# 8_pin_plank.net
KiCad netlist of a schematic drawn in EAGLE
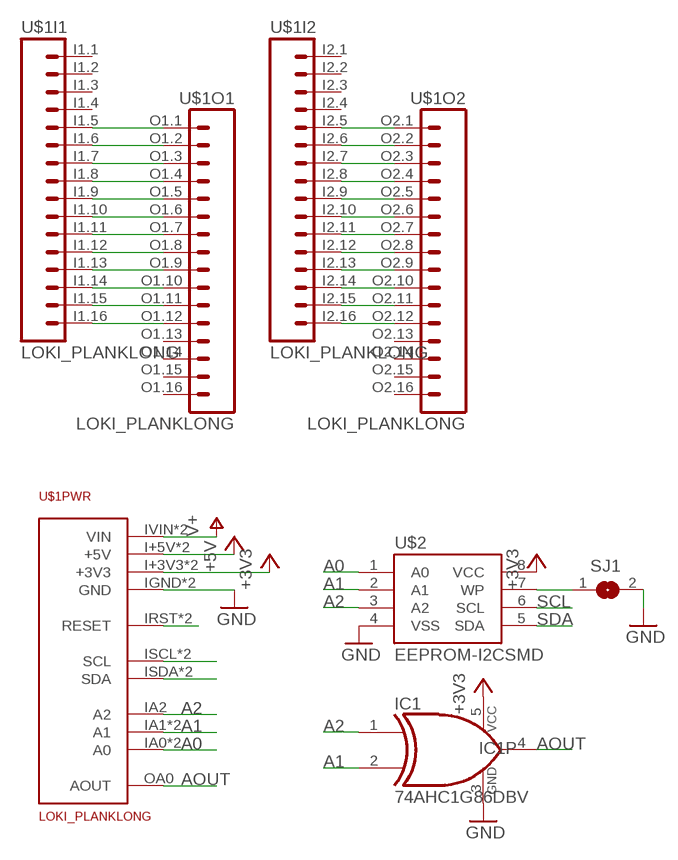
[diagram p0: schematic, sheet 1]

(export (version "E")
  (design (tool "Eeschema 10.0.6"))
  (components
    (comp (ref "IC1")
      (value "74AHC1G86DBV")
      (footprint "eagle-import:SOT23-5")
      (libsource (lib "eagle-import") (part "741G86DBVAHC"))
    )
    (comp (ref "SJ1") (value "SJ") (footprint "eagle-import:SJ") (libsource (lib "eagle-import") (part "SJ")))
    (comp (ref "U$1")
      (value "LOKI_PLANKLONG")
      (footprint "eagle-import:PLANK_LONG")
      (libsource (lib "eagle-import") (part "LOKI_PLANKLONG"))
    )
    (comp (ref "U$2")
      (value "EEPROM-I2CSMD")
      (footprint "eagle-import:SO08")
      (libsource (lib "eagle-import") (part "EEPROM-I2CSMD"))
    )
  )
  (nets
    (net (code "1") (name "+3V3") (class "Default")
      (node (ref "IC1") (pin "5") (pinfunction "VCC_5") (pintype "power_in"))
      (node (ref "U$1") (pin "I+3V3") (pinfunction "+3V3_I+3V3") (pintype "power_in"))
      (node (ref "U$1") (pin "O+3V3") (pinfunction "+3V3_O+3V3") (pintype "power_in"))
      (node (ref "U$2") (pin "8") (pinfunction "VCC_8") (pintype "power_in"))
    )
    (net (code "2") (name "+5V") (class "Default")
      (node (ref "U$1") (pin "I+5V") (pinfunction "+5V_I+5V") (pintype "power_in"))
      (node (ref "U$1") (pin "O+5V") (pinfunction "+5V_O+5V") (pintype "power_in"))
    )
    (net (code "3") (name "/A0") (class "Default")
      (node (ref "U$1") (pin "IA0") (pinfunction "A0_IA0") (pintype "output"))
      (node (ref "U$1") (pin "OA1") (pinfunction "A0_OA1") (pintype "output"))
      (node (ref "U$2") (pin "1") (pinfunction "A0_1") (pintype "bidirectional"))
    )
    (net (code "4") (name "/A1") (class "Default")
      (node (ref "IC1") (pin "2") (pinfunction "I1_2") (pintype "input"))
      (node (ref "U$1") (pin "IA1") (pinfunction "A1_IA1") (pintype "output"))
      (node (ref "U$1") (pin "OA2") (pinfunction "A1_OA2") (pintype "output"))
      (node (ref "U$2") (pin "2") (pinfunction "A1_2") (pintype "bidirectional"))
    )
    (net (code "5") (name "/A2") (class "Default")
      (node (ref "IC1") (pin "1") (pinfunction "I0_1") (pintype "input"))
      (node (ref "U$1") (pin "IA2") (pinfunction "A2_IA2") (pintype "output"))
      (node (ref "U$2") (pin "3") (pinfunction "A2_3") (pintype "bidirectional"))
    )
    (net (code "6") (name "/AOUT") (class "Default")
      (node (ref "IC1") (pin "4") (pinfunction "O_4") (pintype "output"))
      (node (ref "U$1") (pin "OA0") (pinfunction "AOUT_OA0") (pintype "input"))
    )
    (net (code "7") (name "/SCL") (class "Default")
      (node (ref "U$1") (pin "ISCL") (pinfunction "SCL_ISCL") (pintype "bidirectional"))
      (node (ref "U$1") (pin "OSCL") (pinfunction "SCL_OSCL") (pintype "bidirectional"))
      (node (ref "U$2") (pin "6") (pinfunction "SCL_6") (pintype "bidirectional"))
    )
    (net (code "8") (name "/SDA") (class "Default")
      (node (ref "U$1") (pin "ISDA") (pinfunction "SDA_ISDA") (pintype "bidirectional"))
      (node (ref "U$1") (pin "OSDA") (pinfunction "SDA_OSDA") (pintype "bidirectional"))
      (node (ref "U$2") (pin "5") (pinfunction "SDA_5") (pintype "bidirectional"))
    )
    (net (code "9") (name "GND") (class "Default")
      (node (ref "IC1") (pin "3") (pinfunction "GND_3") (pintype "power_in"))
      (node (ref "SJ1") (pin "2") (pinfunction "2_2") (pintype "passive"))
      (node (ref "U$1") (pin "IGND") (pinfunction "GND_IGND") (pintype "power_in"))
      (node (ref "U$1") (pin "OGND") (pinfunction "GND_OGND") (pintype "power_in"))
      (node (ref "U$2") (pin "4") (pinfunction "VSS_4") (pintype "power_in"))
    )
    (net (code "10") (name "Net-(U$1A-5)") (class "Default")
      (node (ref "U$1") (pin "I1.5") (pinfunction "5_I1.5") (pintype "passive"))
      (node (ref "U$1") (pin "O1.1") (pinfunction "1_O1.1") (pintype "passive"))
    )
    (net (code "11") (name "Net-(U$1A-6)") (class "Default")
      (node (ref "U$1") (pin "I1.6") (pinfunction "6_I1.6") (pintype "passive"))
      (node (ref "U$1") (pin "O1.2") (pinfunction "2_O1.2") (pintype "passive"))
    )
    (net (code "12") (name "Net-(U$1A-7)") (class "Default")
      (node (ref "U$1") (pin "I1.7") (pinfunction "7_I1.7") (pintype "passive"))
      (node (ref "U$1") (pin "O1.3") (pinfunction "3_O1.3") (pintype "passive"))
    )
    (net (code "13") (name "Net-(U$1A-8)") (class "Default")
      (node (ref "U$1") (pin "I1.8") (pinfunction "8_I1.8") (pintype "passive"))
      (node (ref "U$1") (pin "O1.4") (pinfunction "4_O1.4") (pintype "passive"))
    )
    (net (code "14") (name "Net-(U$1A-9)") (class "Default")
      (node (ref "U$1") (pin "I1.9") (pinfunction "9_I1.9") (pintype "passive"))
      (node (ref "U$1") (pin "O1.5") (pinfunction "5_O1.5") (pintype "passive"))
    )
    (net (code "15") (name "Net-(U$1A-10)") (class "Default")
      (node (ref "U$1") (pin "I1.10") (pinfunction "10_I1.10") (pintype "passive"))
      (node (ref "U$1") (pin "O1.6") (pinfunction "6_O1.6") (pintype "passive"))
    )
    (net (code "16") (name "Net-(U$1A-11)") (class "Default")
      (node (ref "U$1") (pin "I1.11") (pinfunction "11_I1.11") (pintype "passive"))
      (node (ref "U$1") (pin "O1.7") (pinfunction "7_O1.7") (pintype "passive"))
    )
    (net (code "17") (name "Net-(U$1A-12)") (class "Default")
      (node (ref "U$1") (pin "I1.12") (pinfunction "12_I1.12") (pintype "passive"))
      (node (ref "U$1") (pin "O1.8") (pinfunction "8_O1.8") (pintype "passive"))
    )
    (net (code "18") (name "Net-(U$1A-13)") (class "Default")
      (node (ref "U$1") (pin "I1.13") (pinfunction "13_I1.13") (pintype "passive"))
      (node (ref "U$1") (pin "O1.9") (pinfunction "9_O1.9") (pintype "passive"))
    )
    (net (code "19") (name "Net-(U$1A-14)") (class "Default")
      (node (ref "U$1") (pin "I1.14") (pinfunction "14_I1.14") (pintype "passive"))
      (node (ref "U$1") (pin "O1.10") (pinfunction "10_O1.10") (pintype "passive"))
    )
    (net (code "20") (name "Net-(U$1A-15)") (class "Default")
      (node (ref "U$1") (pin "I1.15") (pinfunction "15_I1.15") (pintype "passive"))
      (node (ref "U$1") (pin "O1.11") (pinfunction "11_O1.11") (pintype "passive"))
    )
    (net (code "21") (name "Net-(U$1A-16)") (class "Default")
      (node (ref "U$1") (pin "I1.16") (pinfunction "16_I1.16") (pintype "passive"))
      (node (ref "U$1") (pin "O1.12") (pinfunction "12_O1.12") (pintype "passive"))
    )
    (net (code "22") (name "Net-(U$1B-5)") (class "Default")
      (node (ref "U$1") (pin "I2.5") (pinfunction "5_I2.5") (pintype "passive"))
      (node (ref "U$1") (pin "O2.1") (pinfunction "1_O2.1") (pintype "passive"))
    )
    (net (code "23") (name "Net-(U$1B-6)") (class "Default")
      (node (ref "U$1") (pin "I2.6") (pinfunction "6_I2.6") (pintype "passive"))
      (node (ref "U$1") (pin "O2.2") (pinfunction "2_O2.2") (pintype "passive"))
    )
    (net (code "24") (name "Net-(U$1B-7)") (class "Default")
      (node (ref "U$1") (pin "I2.7") (pinfunction "7_I2.7") (pintype "passive"))
      (node (ref "U$1") (pin "O2.3") (pinfunction "3_O2.3") (pintype "passive"))
    )
    (net (code "25") (name "Net-(U$1B-8)") (class "Default")
      (node (ref "U$1") (pin "I2.8") (pinfunction "8_I2.8") (pintype "passive"))
      (node (ref "U$1") (pin "O2.4") (pinfunction "4_O2.4") (pintype "passive"))
    )
    (net (code "26") (name "Net-(U$1B-9)") (class "Default")
      (node (ref "U$1") (pin "I2.9") (pinfunction "9_I2.9") (pintype "passive"))
      (node (ref "U$1") (pin "O2.5") (pinfunction "5_O2.5") (pintype "passive"))
    )
    (net (code "27") (name "Net-(U$1B-10)") (class "Default")
      (node (ref "U$1") (pin "I2.10") (pinfunction "10_I2.10") (pintype "passive"))
      (node (ref "U$1") (pin "O2.6") (pinfunction "6_O2.6") (pintype "passive"))
    )
    (net (code "28") (name "Net-(U$1B-11)") (class "Default")
      (node (ref "U$1") (pin "I2.11") (pinfunction "11_I2.11") (pintype "passive"))
      (node (ref "U$1") (pin "O2.7") (pinfunction "7_O2.7") (pintype "passive"))
    )
    (net (code "29") (name "Net-(U$1B-12)") (class "Default")
      (node (ref "U$1") (pin "I2.12") (pinfunction "12_I2.12") (pintype "passive"))
      (node (ref "U$1") (pin "O2.8") (pinfunction "8_O2.8") (pintype "passive"))
    )
    (net (code "30") (name "Net-(U$1B-13)") (class "Default")
      (node (ref "U$1") (pin "I2.13") (pinfunction "13_I2.13") (pintype "passive"))
      (node (ref "U$1") (pin "O2.9") (pinfunction "9_O2.9") (pintype "passive"))
    )
    (net (code "31") (name "Net-(U$1B-14)") (class "Default")
      (node (ref "U$1") (pin "I2.14") (pinfunction "14_I2.14") (pintype "passive"))
      (node (ref "U$1") (pin "O2.10") (pinfunction "10_O2.10") (pintype "passive"))
    )
    (net (code "32") (name "Net-(U$1B-15)") (class "Default")
      (node (ref "U$1") (pin "I2.15") (pinfunction "15_I2.15") (pintype "passive"))
      (node (ref "U$1") (pin "O2.11") (pinfunction "11_O2.11") (pintype "passive"))
    )
    (net (code "33") (name "Net-(U$1B-16)") (class "Default")
      (node (ref "U$1") (pin "I2.16") (pinfunction "16_I2.16") (pintype "passive"))
      (node (ref "U$1") (pin "O2.12") (pinfunction "12_O2.12") (pintype "passive"))
    )
    (net (code "34") (name "Net-(U$1E-RESET-PadIRST)") (class "Default")
      (node (ref "U$1") (pin "IRST") (pinfunction "RESET_IRST") (pintype "input"))
      (node (ref "U$1") (pin "ORST") (pinfunction "RESET_ORST") (pintype "input"))
    )
    (net (code "35") (name "Net-(U$2-WP)") (class "Default")
      (node (ref "SJ1") (pin "1") (pinfunction "1_1") (pintype "passive"))
      (node (ref "U$2") (pin "7") (pinfunction "WP_7") (pintype "bidirectional"))
    )
    (net (code "36") (name "V+") (class "Default")
      (node (ref "U$1") (pin "IVIN") (pinfunction "VIN_IVIN") (pintype "power_in"))
      (node (ref "U$1") (pin "OVIN") (pinfunction "VIN_OVIN") (pintype "power_in"))
    )
    (net (code "37") (name "unconnected-(U$1A-1-PadI1.1)") (class "Default")
      (node (ref "U$1") (pin "I1.1") (pinfunction "1_I1.1") (pintype "passive"))
    )
    (net (code "38") (name "unconnected-(U$1A-2-PadI1.2)") (class "Default")
      (node (ref "U$1") (pin "I1.2") (pinfunction "2_I1.2") (pintype "passive"))
    )
    (net (code "39") (name "unconnected-(U$1A-3-PadI1.3)") (class "Default")
      (node (ref "U$1") (pin "I1.3") (pinfunction "3_I1.3") (pintype "passive"))
    )
    (net (code "40") (name "unconnected-(U$1A-4-PadI1.4)") (class "Default")
      (node (ref "U$1") (pin "I1.4") (pinfunction "4_I1.4") (pintype "passive"))
    )
    (net (code "41") (name "unconnected-(U$1B-1-PadI2.1)") (class "Default")
      (node (ref "U$1") (pin "I2.1") (pinfunction "1_I2.1") (pintype "passive"))
    )
    (net (code "42") (name "unconnected-(U$1B-2-PadI2.2)") (class "Default")
      (node (ref "U$1") (pin "I2.2") (pinfunction "2_I2.2") (pintype "passive"))
    )
    (net (code "43") (name "unconnected-(U$1B-3-PadI2.3)") (class "Default")
      (node (ref "U$1") (pin "I2.3") (pinfunction "3_I2.3") (pintype "passive"))
    )
    (net (code "44") (name "unconnected-(U$1B-4-PadI2.4)") (class "Default")
      (node (ref "U$1") (pin "I2.4") (pinfunction "4_I2.4") (pintype "passive"))
    )
    (net (code "45") (name "unconnected-(U$1C-13-PadO1.13)") (class "Default")
      (node (ref "U$1") (pin "O1.13") (pinfunction "13_O1.13") (pintype "passive"))
    )
    (net (code "46") (name "unconnected-(U$1C-14-PadO1.14)") (class "Default")
      (node (ref "U$1") (pin "O1.14") (pinfunction "14_O1.14") (pintype "passive"))
    )
    (net (code "47") (name "unconnected-(U$1C-15-PadO1.15)") (class "Default")
      (node (ref "U$1") (pin "O1.15") (pinfunction "15_O1.15") (pintype "passive"))
    )
    (net (code "48") (name "unconnected-(U$1C-16-PadO1.16)") (class "Default")
      (node (ref "U$1") (pin "O1.16") (pinfunction "16_O1.16") (pintype "passive"))
    )
    (net (code "49") (name "unconnected-(U$1D-13-PadO2.13)") (class "Default")
      (node (ref "U$1") (pin "O2.13") (pinfunction "13_O2.13") (pintype "passive"))
    )
    (net (code "50") (name "unconnected-(U$1D-14-PadO2.14)") (class "Default")
      (node (ref "U$1") (pin "O2.14") (pinfunction "14_O2.14") (pintype "passive"))
    )
    (net (code "51") (name "unconnected-(U$1D-15-PadO2.15)") (class "Default")
      (node (ref "U$1") (pin "O2.15") (pinfunction "15_O2.15") (pintype "passive"))
    )
    (net (code "52") (name "unconnected-(U$1D-16-PadO2.16)") (class "Default")
      (node (ref "U$1") (pin "O2.16") (pinfunction "16_O2.16") (pintype "passive"))
    )
  )
)
